# ISO_UARTc.net
KiCad netlist of a schematic drawn in Altium Designer
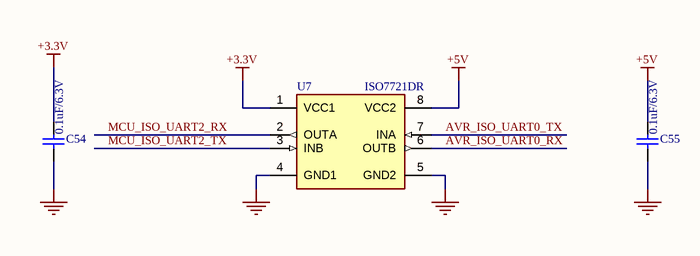
[diagram p0: ISO_UARTc.SchDoc]

(export (version "E")
  (design (tool "Eeschema 10.0.6"))
  (components
    (comp (ref "C54")
      (value "0.1uF/6.3V")
      (footprint "CAP_C_1608X80")
      (description "CAPC")
      (libsource (lib "Altium_Lib_by_KhueNguyenCreator") (part "Tu 0402 33nF 10V"))
    )
    (comp (ref "C55")
      (value "0.1uF/6.3V")
      (footprint "CAP_C_1608X80")
      (description "CAPC")
      (libsource (lib "Altium_Lib_by_KhueNguyenCreator") (part "Tu 0402 33nF 10V"))
    )
    (comp (ref "U7")
      (value "ISO7721DR")
      (footprint "SOIC127P602X173-8N")
      (description "Robust EMC, dual-channel, 1/1, reinforced digital isolator 8-SOIC -55 to 125")
      (libsource (lib "ISO7721DR") (part "ISO7721DR"))
    )
  )
  (nets
    (net (code "1") (name "+3.3V") (class "Default")
      (node (ref "C54") (pin "1") (pinfunction "1_1") (pintype "passive"))
      (node (ref "U7") (pin "1") (pinfunction "VCC1_1") (pintype "power_in"))
    )
    (net (code "2") (name "+5V") (class "Default")
      (node (ref "C55") (pin "1") (pinfunction "1_1") (pintype "passive"))
      (node (ref "U7") (pin "8") (pinfunction "VCC2_8") (pintype "power_in"))
    )
    (net (code "3") (name "/AVR_ISO_UART0_RX") (class "Default")
      (node (ref "U7") (pin "6") (pinfunction "OUTB_6") (pintype "output"))
    )
    (net (code "4") (name "/AVR_ISO_UART0_TX") (class "Default")
      (node (ref "U7") (pin "7") (pinfunction "INA_7") (pintype "input"))
    )
    (net (code "5") (name "/MCU_ISO_UART2_RX") (class "Default")
      (node (ref "U7") (pin "2") (pinfunction "OUTA_2") (pintype "output"))
    )
    (net (code "6") (name "/MCU_ISO_UART2_TX") (class "Default")
      (node (ref "U7") (pin "3") (pinfunction "INB_3") (pintype "input"))
    )
    (net (code "7") (name "GND") (class "Default")
      (node (ref "C54") (pin "2") (pinfunction "2_2") (pintype "passive"))
      (node (ref "C55") (pin "2") (pinfunction "2_2") (pintype "passive"))
      (node (ref "U7") (pin "4") (pinfunction "GND1_4") (pintype "power_in"))
      (node (ref "U7") (pin "5") (pinfunction "GND2_5") (pintype "power_in"))
    )
  )
)
